# Sounder_Buzzer.net
KiCad netlist of a schematic drawn in Altium Designer
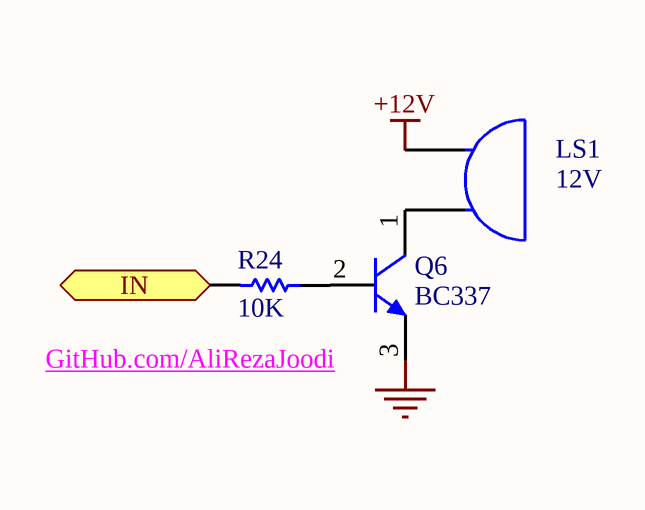
[diagram p0: Sounder_Buzzer.SchDoc]

(export (version "E")
  (design (tool "Eeschema 10.0.6"))
  (components
    (comp (ref "LS1")
      (value "12V")
      (footprint "RB_7.62mm")
      (description "Sounder")
      (fields
        (field (name "MANUFACTURER") "Generic Components")
        (field (name "Comment") "Buzzer")
        (field (name "PUBLISHER") "Altium Limited")
      )
      (libsource (lib "my Libraries") (part "Buzzer"))
    )
    (comp (ref "Q6")
      (value "BC337")
      (footprint "TO92C")
      (description "NPN Bipolar Transistor")
      (fields
        (field (name "MANUFACTURER") "Generic Components")
        (field (name "Comment") "NPN")
        (field (name "PUBLISHER") "Altium Limited")
      )
      (libsource (lib "Miscellaneous Devices") (part "NPN"))
    )
    (comp (ref "R24")
      (value "10K")
      (footprint "AXIAL-0.4")
      (description "Resistor")
      (fields (field (name "Comment") "Res1") (field (name "PUBLISHER") "Altium Limited"))
      (libsource (lib "Miscellaneous Devices") (part "Res1"))
    )
  )
  (nets
    (net (code "1") (name "+12V") (class "Default")
      (node (ref "LS1") (pin "1") (pinfunction "A_1") (pintype "passive"))
    )
    (net (code "2") (name "/IN") (class "Default")
      (node (ref "R24") (pin "2") (pinfunction "2_2") (pintype "passive"))
    )
    (net (code "3") (name "GND") (class "Default")
      (node (ref "Q6") (pin "3") (pinfunction "E_3") (pintype "passive"))
    )
    (net (code "4") (name "Net-(LS1-B)") (class "Default")
      (node (ref "LS1") (pin "2") (pinfunction "B_2") (pintype "passive"))
      (node (ref "Q6") (pin "1") (pinfunction "C_1") (pintype "passive"))
    )
    (net (code "5") (name "Net-(Q6-B)") (class "Default")
      (node (ref "Q6") (pin "2") (pinfunction "B_2") (pintype "passive"))
      (node (ref "R24") (pin "1") (pinfunction "1_1") (pintype "passive"))
    )
  )
)
